# sunalarm.net
KiCad netlist of a schematic drawn in EAGLE
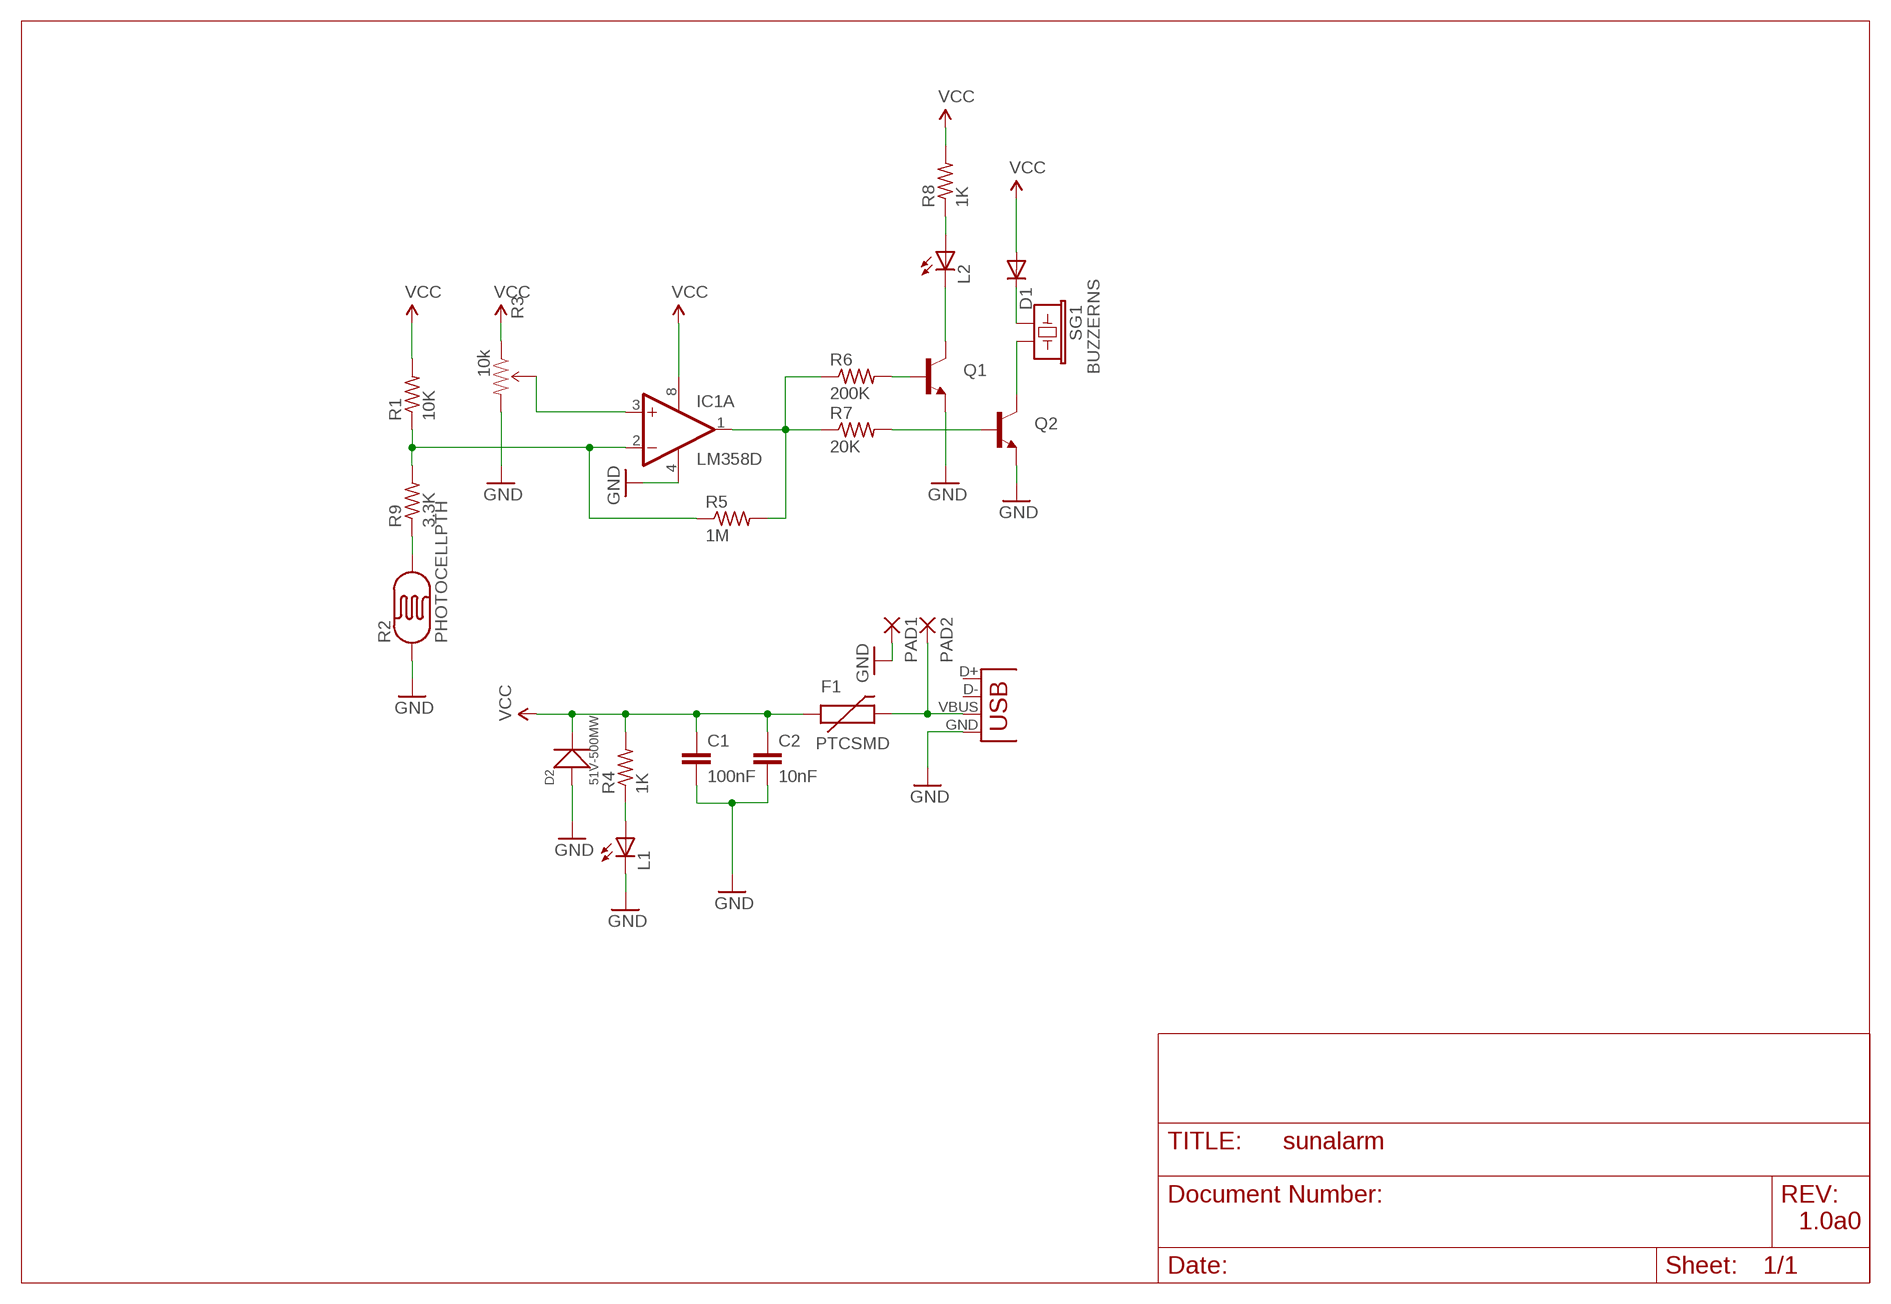
[diagram p0: schematic, sheet 1]

(export (version "E")
  (design (tool "Eeschema 10.0.6"))
  (components
    (comp (ref "C1")
      (value "100nF")
      (footprint "eagle-import:0603-CAP")
      (libsource (lib "eagle-import") (part "CAP0603-CAP"))
    )
    (comp (ref "C2")
      (value "10nF")
      (footprint "eagle-import:0603-CAP")
      (libsource (lib "eagle-import") (part "CAP0603-CAP"))
    )
    (comp (ref "D1")
      (value "DIODESOD")
      (footprint "eagle-import:SOD-323")
      (libsource (lib "eagle-import") (part "DIODESOD"))
    )
    (comp (ref "D2")
      (value "51V-500MW")
      (footprint "eagle-import:SOD-123")
      (fields (field (name "MPN") "MMSZ4689-V-GS08"))
      (libsource (lib "eagle-import") (part "SMD-DIODE-ZENER-51.V-500MW(SOD-123)"))
    )
    (comp (ref "F1")
      (value "PTCSMD")
      (footprint "eagle-import:PTC-1206")
      (libsource (lib "eagle-import") (part "PTCSMD"))
    )
    (comp (ref "IC1")
      (value "LM358D")
      (footprint "eagle-import:SO08")
      (libsource (lib "eagle-import") (part "LM358D"))
    )
    (comp (ref "L1")
      (value "LED0603")
      (footprint "eagle-import:LED-0603")
      (libsource (lib "eagle-import") (part "LED0603"))
    )
    (comp (ref "L2")
      (value "LED0603")
      (footprint "eagle-import:LED-0603")
      (libsource (lib "eagle-import") (part "LED0603"))
    )
    (comp (ref "PAD1")
      (value "WIREPADSMD1,27-254")
      (footprint "eagle-import:SMD1,27-2,54")
      (libsource (lib "eagle-import") (part "WIREPADSMD1,27-254"))
    )
    (comp (ref "PAD2")
      (value "WIREPADSMD1,27-254")
      (footprint "eagle-import:SMD1,27-2,54")
      (libsource (lib "eagle-import") (part "WIREPADSMD1,27-254"))
    )
    (comp (ref "Q1")
      (value "TRANSISTOR_NPNSOT23")
      (footprint "eagle-import:SOT23")
      (libsource (lib "eagle-import") (part "TRANSISTOR_NPNSOT23"))
    )
    (comp (ref "Q2")
      (value "TRANSISTOR_NPNSOT23")
      (footprint "eagle-import:SOT23")
      (libsource (lib "eagle-import") (part "TRANSISTOR_NPNSOT23"))
    )
    (comp (ref "R1")
      (value "10K")
      (footprint "eagle-import:R0603")
      (libsource (lib "eagle-import") (part "R-US_R0603"))
    )
    (comp (ref "R2")
      (value "PHOTOCELLPTH")
      (footprint "eagle-import:PHOTOCELL")
      (libsource (lib "eagle-import") (part "PHOTOCELLPTH"))
    )
    (comp (ref "R3")
      (value "10k")
      (footprint "eagle-import:TRIMPOT-3MM")
      (libsource (lib "eagle-import") (part "TRIMPOTRES-09285"))
    )
    (comp (ref "R4")
      (value "1K")
      (footprint "eagle-import:R0603")
      (libsource (lib "eagle-import") (part "R-US_R0603"))
    )
    (comp (ref "R5")
      (value "1M")
      (footprint "eagle-import:R0603")
      (libsource (lib "eagle-import") (part "R-US_R0603"))
    )
    (comp (ref "R6")
      (value "200K")
      (footprint "eagle-import:R0603")
      (libsource (lib "eagle-import") (part "R-US_R0603"))
    )
    (comp (ref "R7")
      (value "20K")
      (footprint "eagle-import:R0603")
      (libsource (lib "eagle-import") (part "R-US_R0603"))
    )
    (comp (ref "R8")
      (value "1K")
      (footprint "eagle-import:R0603")
      (libsource (lib "eagle-import") (part "R-US_R0603"))
    )
    (comp (ref "R9")
      (value "3.3K")
      (footprint "eagle-import:R0603")
      (libsource (lib "eagle-import") (part "R-US_R0603"))
    )
    (comp (ref "SG1")
      (value "BUZZERNS")
      (footprint "eagle-import:BUZZER-12MM-NS")
      (libsource (lib "eagle-import") (part "BUZZERNS"))
    )
    (comp (ref "X1")
      (value "USB-MICROB")
      (footprint "eagle-import:USB-MICROB")
      (libsource (lib "eagle-import") (part "USB-MICROB"))
    )
  )
  (nets
    (net (code "1") (name "GND") (class "Default")
      (node (ref "C1") (pin "2") (pinfunction "2_2") (pintype "passive"))
      (node (ref "C2") (pin "2") (pinfunction "2_2") (pintype "passive"))
      (node (ref "D2") (pin "+") (pinfunction "+_+") (pintype "passive"))
      (node (ref "IC1") (pin "4") (pinfunction "V-_4") (pintype "power_in"))
      (node (ref "L1") (pin "C") (pinfunction "C_C") (pintype "passive"))
      (node (ref "PAD1") (pin "1") (pinfunction "P_1") (pintype "passive"))
      (node (ref "Q1") (pin "2") (pinfunction "E_2") (pintype "passive"))
      (node (ref "Q2") (pin "2") (pinfunction "E_2") (pintype "passive"))
      (node (ref "R2") (pin "1") (pinfunction "P$1_1") (pintype "bidirectional"))
      (node (ref "R3") (pin "3") (pinfunction "CW_3") (pintype "passive"))
      (node (ref "X1") (pin "GND") (pinfunction "GND_GND") (pintype "bidirectional"))
    )
    (net (code "2") (name "Net-(D1-C)") (class "Default")
      (node (ref "D1") (pin "1") (pinfunction "C_1") (pintype "passive"))
      (node (ref "SG1") (pin "+") (pinfunction "1_+") (pintype "passive"))
    )
    (net (code "3") (name "Net-(IC1A-+IN)") (class "Default")
      (node (ref "IC1") (pin "3") (pinfunction "+IN_3") (pintype "input"))
      (node (ref "R3") (pin "2") (pinfunction "WIPER_2") (pintype "passive"))
    )
    (net (code "4") (name "Net-(IC1A--IN)") (class "Default")
      (node (ref "IC1") (pin "2") (pinfunction "-IN_2") (pintype "input"))
      (node (ref "R1") (pin "1") (pinfunction "1_1") (pintype "passive"))
      (node (ref "R5") (pin "1") (pinfunction "1_1") (pintype "passive"))
      (node (ref "R9") (pin "2") (pinfunction "2_2") (pintype "passive"))
    )
    (net (code "5") (name "Net-(IC1A-OUT)") (class "Default")
      (node (ref "IC1") (pin "1") (pinfunction "OUT_1") (pintype "output"))
      (node (ref "R5") (pin "2") (pinfunction "2_2") (pintype "passive"))
      (node (ref "R6") (pin "1") (pinfunction "1_1") (pintype "passive"))
      (node (ref "R7") (pin "1") (pinfunction "1_1") (pintype "passive"))
    )
    (net (code "6") (name "Net-(L1-PadA)") (class "Default")
      (node (ref "L1") (pin "A") (pinfunction "A_A") (pintype "passive"))
      (node (ref "R4") (pin "1") (pinfunction "1_1") (pintype "passive"))
    )
    (net (code "7") (name "Net-(L2-PadA)") (class "Default")
      (node (ref "L2") (pin "A") (pinfunction "A_A") (pintype "passive"))
      (node (ref "R8") (pin "1") (pinfunction "1_1") (pintype "passive"))
    )
    (net (code "8") (name "Net-(PAD2-P)") (class "Default")
      (node (ref "F1") (pin "2") (pinfunction "2_2") (pintype "bidirectional"))
      (node (ref "PAD2") (pin "1") (pinfunction "P_1") (pintype "passive"))
      (node (ref "X1") (pin "VBUS") (pinfunction "VBUS_VBUS") (pintype "bidirectional"))
    )
    (net (code "9") (name "Net-(Q1-B)") (class "Default")
      (node (ref "Q1") (pin "1") (pinfunction "B_1") (pintype "passive"))
      (node (ref "R6") (pin "2") (pinfunction "2_2") (pintype "passive"))
    )
    (net (code "10") (name "Net-(Q1-C)") (class "Default")
      (node (ref "L2") (pin "C") (pinfunction "C_C") (pintype "passive"))
      (node (ref "Q1") (pin "3") (pinfunction "C_3") (pintype "passive"))
    )
    (net (code "11") (name "Net-(Q2-B)") (class "Default")
      (node (ref "Q2") (pin "1") (pinfunction "B_1") (pintype "passive"))
      (node (ref "R7") (pin "2") (pinfunction "2_2") (pintype "passive"))
    )
    (net (code "12") (name "Net-(Q2-C)") (class "Default")
      (node (ref "Q2") (pin "3") (pinfunction "C_3") (pintype "passive"))
      (node (ref "SG1") (pin "-") (pinfunction "2_-") (pintype "passive"))
    )
    (net (code "13") (name "Net-(R2-P$2)") (class "Default")
      (node (ref "R2") (pin "2") (pinfunction "P$2_2") (pintype "bidirectional"))
      (node (ref "R9") (pin "1") (pinfunction "1_1") (pintype "passive"))
    )
    (net (code "14") (name "VCC") (class "Default")
      (node (ref "C1") (pin "1") (pinfunction "1_1") (pintype "passive"))
      (node (ref "C2") (pin "1") (pinfunction "1_1") (pintype "passive"))
      (node (ref "D1") (pin "2") (pinfunction "A_2") (pintype "passive"))
      (node (ref "D2") (pin "-") (pinfunction "-_-") (pintype "passive"))
      (node (ref "F1") (pin "1") (pinfunction "1_1") (pintype "bidirectional"))
      (node (ref "IC1") (pin "8") (pinfunction "V+_8") (pintype "power_in"))
      (node (ref "R1") (pin "2") (pinfunction "2_2") (pintype "passive"))
      (node (ref "R3") (pin "1") (pinfunction "CCW_1") (pintype "passive"))
      (node (ref "R4") (pin "2") (pinfunction "2_2") (pintype "passive"))
      (node (ref "R8") (pin "2") (pinfunction "2_2") (pintype "passive"))
    )
    (net (code "15") (name "unconnected-(X1-PadD+)") (class "Default")
      (node (ref "X1") (pin "D+") (pinfunction "D+_D+") (pintype "bidirectional"))
    )
    (net (code "16") (name "unconnected-(X1-PadD-)") (class "Default")
      (node (ref "X1") (pin "D-") (pinfunction "D-_D-") (pintype "bidirectional"))
    )
  )
)
